# capacitors_voltage_divider.net
KiCad netlist of a schematic drawn in EAGLE
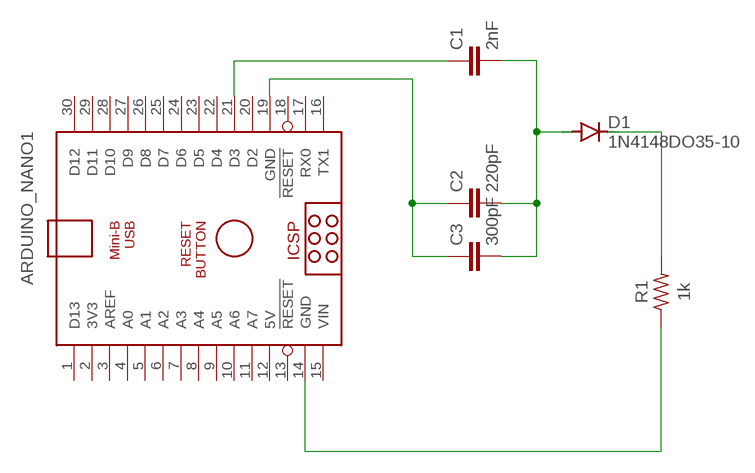
[diagram p0: schematic, sheet 1]

(export (version "E")
  (design (tool "Eeschema 10.0.6"))
  (components
    (comp (ref "ARDUINO_NANO1")
      (value "ARDUINO_NANO")
      (footprint "eagle-import:ARDUINO_NANO")
      (libsource (lib "eagle-import") (part "ARDUINO_NANO"))
    )
    (comp (ref "C1")
      (value "2nF")
      (footprint "eagle-import:C2.5-3")
      (libsource (lib "eagle-import") (part "C2,5-3"))
    )
    (comp (ref "C2")
      (value "220pF")
      (footprint "eagle-import:C2.5-3")
      (libsource (lib "eagle-import") (part "C2,5-3"))
    )
    (comp (ref "C3")
      (value "300pF")
      (footprint "eagle-import:C2.5-3")
      (libsource (lib "eagle-import") (part "C2,5-3"))
    )
    (comp (ref "D1")
      (value "1N4148DO35-10")
      (footprint "eagle-import:DO35-10")
      (libsource (lib "eagle-import") (part "1N4148DO35-10"))
    )
    (comp (ref "R1")
      (value "1k")
      (footprint "eagle-import:RESAD724W46L381D178B")
      (libsource (lib "eagle-import") (part "R-USAXIAL-7.2MM-PITCH_"))
    )
  )
  (nets
    (net (code "1") (name "/5V") (class "Default")
      (node (ref "ARDUINO_NANO1") (pin "12") (pinfunction "5V_12") (pintype "power_in"))
    )
    (net (code "2") (name "/VIN") (class "Default")
      (node (ref "ARDUINO_NANO1") (pin "15") (pinfunction "VIN_15") (pintype "power_in"))
    )
    (net (code "3") (name "Net-(ARDUINO_NANO1-D3)") (class "Default")
      (node (ref "ARDUINO_NANO1") (pin "21") (pinfunction "D3_21") (pintype "bidirectional"))
      (node (ref "C1") (pin "1") (pinfunction "1_1") (pintype "passive"))
    )
    (net (code "4") (name "Net-(ARDUINO_NANO1-GND-Pad14)") (class "Default")
      (node (ref "ARDUINO_NANO1") (pin "14") (pinfunction "GND_14") (pintype "power_in"))
      (node (ref "R1") (pin "1") (pinfunction "1_1") (pintype "passive"))
    )
    (net (code "5") (name "Net-(ARDUINO_NANO1-GND-Pad19)") (class "Default")
      (node (ref "ARDUINO_NANO1") (pin "19") (pinfunction "GND_19") (pintype "power_in"))
      (node (ref "C2") (pin "1") (pinfunction "1_1") (pintype "passive"))
      (node (ref "C3") (pin "1") (pinfunction "1_1") (pintype "passive"))
    )
    (net (code "6") (name "Net-(C1-Pad2)") (class "Default")
      (node (ref "C1") (pin "2") (pinfunction "2_2") (pintype "passive"))
      (node (ref "C2") (pin "2") (pinfunction "2_2") (pintype "passive"))
      (node (ref "C3") (pin "2") (pinfunction "2_2") (pintype "passive"))
      (node (ref "D1") (pin "A") (pinfunction "A_A") (pintype "passive"))
    )
    (net (code "7") (name "Net-(D1-PadC)") (class "Default")
      (node (ref "D1") (pin "C") (pinfunction "C_C") (pintype "passive"))
      (node (ref "R1") (pin "2") (pinfunction "2_2") (pintype "passive"))
    )
    (net (code "8") (name "unconnected-(ARDUINO_NANO1-3V3-Pad2)") (class "Default")
      (node (ref "ARDUINO_NANO1") (pin "2") (pinfunction "3V3_2") (pintype "output"))
    )
    (net (code "9") (name "unconnected-(ARDUINO_NANO1-A0-Pad4)") (class "Default")
      (node (ref "ARDUINO_NANO1") (pin "4") (pinfunction "A0_4") (pintype "bidirectional"))
    )
    (net (code "10") (name "unconnected-(ARDUINO_NANO1-A1-Pad5)") (class "Default")
      (node (ref "ARDUINO_NANO1") (pin "5") (pinfunction "A1_5") (pintype "bidirectional"))
    )
    (net (code "11") (name "unconnected-(ARDUINO_NANO1-A2-Pad6)") (class "Default")
      (node (ref "ARDUINO_NANO1") (pin "6") (pinfunction "A2_6") (pintype "bidirectional"))
    )
    (net (code "12") (name "unconnected-(ARDUINO_NANO1-A3-Pad7)") (class "Default")
      (node (ref "ARDUINO_NANO1") (pin "7") (pinfunction "A3_7") (pintype "bidirectional"))
    )
    (net (code "13") (name "unconnected-(ARDUINO_NANO1-A4-Pad8)") (class "Default")
      (node (ref "ARDUINO_NANO1") (pin "8") (pinfunction "A4_8") (pintype "bidirectional"))
    )
    (net (code "14") (name "unconnected-(ARDUINO_NANO1-A5-Pad9)") (class "Default")
      (node (ref "ARDUINO_NANO1") (pin "9") (pinfunction "A5_9") (pintype "bidirectional"))
    )
    (net (code "15") (name "unconnected-(ARDUINO_NANO1-A6-Pad10)") (class "Default")
      (node (ref "ARDUINO_NANO1") (pin "10") (pinfunction "A6_10") (pintype "bidirectional"))
    )
    (net (code "16") (name "unconnected-(ARDUINO_NANO1-A7-Pad11)") (class "Default")
      (node (ref "ARDUINO_NANO1") (pin "11") (pinfunction "A7_11") (pintype "bidirectional"))
    )
    (net (code "17") (name "unconnected-(ARDUINO_NANO1-AREF-Pad3)") (class "Default")
      (node (ref "ARDUINO_NANO1") (pin "3") (pinfunction "AREF_3") (pintype "input"))
    )
    (net (code "18") (name "unconnected-(ARDUINO_NANO1-D2-Pad20)") (class "Default")
      (node (ref "ARDUINO_NANO1") (pin "20") (pinfunction "D2_20") (pintype "bidirectional"))
    )
    (net (code "19") (name "unconnected-(ARDUINO_NANO1-D4-Pad22)") (class "Default")
      (node (ref "ARDUINO_NANO1") (pin "22") (pinfunction "D4_22") (pintype "bidirectional"))
    )
    (net (code "20") (name "unconnected-(ARDUINO_NANO1-D5-Pad23)") (class "Default")
      (node (ref "ARDUINO_NANO1") (pin "23") (pinfunction "D5_23") (pintype "bidirectional"))
    )
    (net (code "21") (name "unconnected-(ARDUINO_NANO1-D6-Pad24)") (class "Default")
      (node (ref "ARDUINO_NANO1") (pin "24") (pinfunction "D6_24") (pintype "bidirectional"))
    )
    (net (code "22") (name "unconnected-(ARDUINO_NANO1-D7-Pad25)") (class "Default")
      (node (ref "ARDUINO_NANO1") (pin "25") (pinfunction "D7_25") (pintype "bidirectional"))
    )
    (net (code "23") (name "unconnected-(ARDUINO_NANO1-D8-Pad26)") (class "Default")
      (node (ref "ARDUINO_NANO1") (pin "26") (pinfunction "D8_26") (pintype "bidirectional"))
    )
    (net (code "24") (name "unconnected-(ARDUINO_NANO1-D9-Pad27)") (class "Default")
      (node (ref "ARDUINO_NANO1") (pin "27") (pinfunction "D9_27") (pintype "bidirectional"))
    )
    (net (code "25") (name "unconnected-(ARDUINO_NANO1-D10-Pad28)") (class "Default")
      (node (ref "ARDUINO_NANO1") (pin "28") (pinfunction "D10_28") (pintype "bidirectional"))
    )
    (net (code "26") (name "unconnected-(ARDUINO_NANO1-D11-Pad29)") (class "Default")
      (node (ref "ARDUINO_NANO1") (pin "29") (pinfunction "D11_29") (pintype "bidirectional"))
    )
    (net (code "27") (name "unconnected-(ARDUINO_NANO1-D12-Pad30)") (class "Default")
      (node (ref "ARDUINO_NANO1") (pin "30") (pinfunction "D12_30") (pintype "bidirectional"))
    )
    (net (code "28") (name "unconnected-(ARDUINO_NANO1-D13-Pad1)") (class "Default")
      (node (ref "ARDUINO_NANO1") (pin "1") (pinfunction "D13_1") (pintype "bidirectional"))
    )
    (net (code "29") (name "unconnected-(ARDUINO_NANO1-RX0-Pad17)") (class "Default")
      (node (ref "ARDUINO_NANO1") (pin "17") (pinfunction "RX0_17") (pintype "bidirectional"))
    )
    (net (code "30") (name "unconnected-(ARDUINO_NANO1-TX1-Pad16)") (class "Default")
      (node (ref "ARDUINO_NANO1") (pin "16") (pinfunction "TX1_16") (pintype "bidirectional"))
    )
    (net (code "31") (name "unconnected-(ARDUINO_NANO1-~{RESET}-Pad13)") (class "Default")
      (node (ref "ARDUINO_NANO1") (pin "13") (pinfunction "~{RESET}_13") (pintype "input"))
    )
    (net (code "32") (name "unconnected-(ARDUINO_NANO1-~{RESET}-Pad18)") (class "Default")
      (node (ref "ARDUINO_NANO1") (pin "18") (pinfunction "~{RESET}_18") (pintype "input"))
    )
  )
)
